# MicroPrimePCB.net
KiCad netlist of a schematic drawn in EAGLE
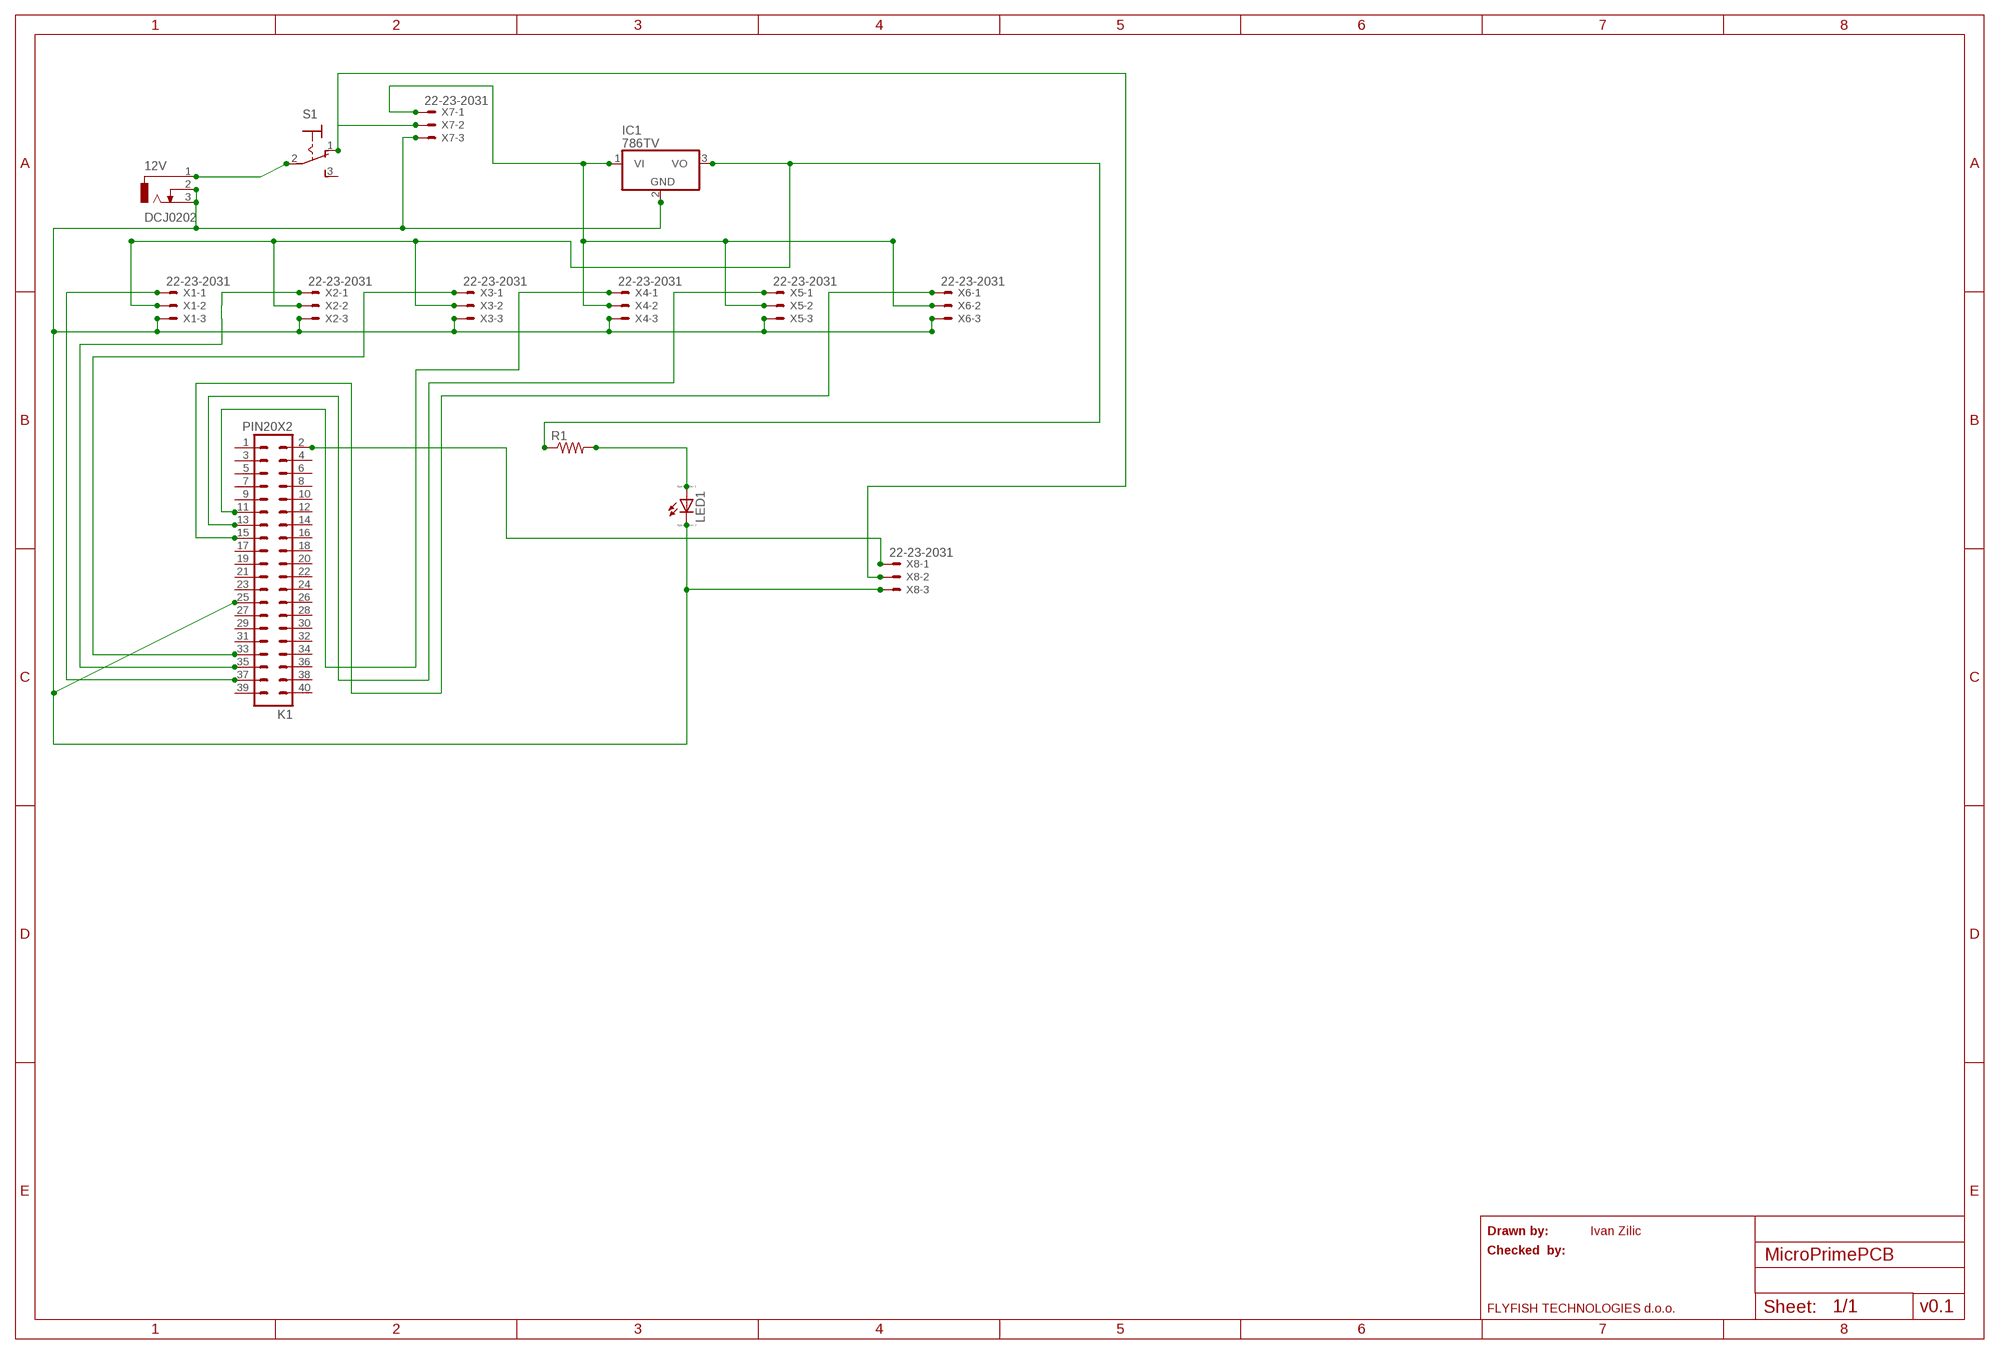
[diagram p0: schematic, sheet 1]

(export (version "E")
  (design (tool "Eeschema 10.0.6"))
  (components
    (comp (ref "12V")
      (value "DCJ0202")
      (footprint "eagle-import:DCJ0202")
      (libsource (lib "eagle-import") (part "DCJ0202"))
    )
    (comp (ref "IC1")
      (value "786TV")
      (footprint "eagle-import:TO220V")
      (libsource (lib "eagle-import") (part "78TV6"))
    )
    (comp (ref "K1")
      (value "PIN20X2")
      (footprint "eagle-import:PIN_20X2")
      (libsource (lib "eagle-import") (part "PIN20X2"))
    )
    (comp (ref "LED1")
      (value "LED_ELD260")
      (footprint "eagle-import:LED_LD260")
      (libsource (lib "eagle-import") (part "LED_ELD260"))
    )
    (comp (ref "R1")
      (value "R-US_0204/7")
      (footprint "eagle-import:0204_7")
      (libsource (lib "eagle-import") (part "R-US_0204/7"))
    )
    (comp (ref "S1")
      (value "320-916")
      (footprint "eagle-import:320-916")
      (libsource (lib "eagle-import") (part "320-916"))
    )
    (comp (ref "X1")
      (value "22-23-2031")
      (footprint "eagle-import:22-23-2031")
      (fields (field (name "MF") "MOLEX"))
      (libsource (lib "eagle-import") (part "22-23-2031"))
    )
    (comp (ref "X2")
      (value "22-23-2031")
      (footprint "eagle-import:22-23-2031")
      (fields (field (name "MF") "MOLEX"))
      (libsource (lib "eagle-import") (part "22-23-2031"))
    )
    (comp (ref "X3")
      (value "22-23-2031")
      (footprint "eagle-import:22-23-2031")
      (fields (field (name "MF") "MOLEX"))
      (libsource (lib "eagle-import") (part "22-23-2031"))
    )
    (comp (ref "X4")
      (value "22-23-2031")
      (footprint "eagle-import:22-23-2031")
      (fields (field (name "MF") "MOLEX"))
      (libsource (lib "eagle-import") (part "22-23-2031"))
    )
    (comp (ref "X5")
      (value "22-23-2031")
      (footprint "eagle-import:22-23-2031")
      (fields (field (name "MF") "MOLEX"))
      (libsource (lib "eagle-import") (part "22-23-2031"))
    )
    (comp (ref "X6")
      (value "22-23-2031")
      (footprint "eagle-import:22-23-2031")
      (fields (field (name "MF") "MOLEX"))
      (libsource (lib "eagle-import") (part "22-23-2031"))
    )
    (comp (ref "X7")
      (value "22-23-2031")
      (footprint "eagle-import:22-23-2031")
      (fields (field (name "MF") "MOLEX"))
      (libsource (lib "eagle-import") (part "22-23-2031"))
    )
    (comp (ref "X8")
      (value "22-23-2031")
      (footprint "eagle-import:22-23-2031")
      (fields (field (name "MF") "MOLEX"))
      (libsource (lib "eagle-import") (part "22-23-2031"))
    )
  )
  (nets
    (net (code "1") (name "Net-(IC1-GND)") (class "Default")
      (node (ref "12V") (pin "2") (pinfunction "2_2") (pintype "passive"))
      (node (ref "12V") (pin "3") (pinfunction "3_3") (pintype "passive"))
      (node (ref "IC1") (pin "2") (pinfunction "GND_2") (pintype "passive"))
      (node (ref "K1") (pin "25") (pinfunction "25_25") (pintype "passive"))
      (node (ref "LED1") (pin "K") (pinfunction "C_K") (pintype "passive"))
      (node (ref "X1") (pin "3") (pinfunction "S_3") (pintype "passive"))
      (node (ref "X2") (pin "3") (pinfunction "S_3") (pintype "passive"))
      (node (ref "X3") (pin "3") (pinfunction "S_3") (pintype "passive"))
      (node (ref "X4") (pin "3") (pinfunction "S_3") (pintype "passive"))
      (node (ref "X5") (pin "3") (pinfunction "S_3") (pintype "passive"))
      (node (ref "X6") (pin "3") (pinfunction "S_3") (pintype "passive"))
      (node (ref "X7") (pin "3") (pinfunction "S_3") (pintype "passive"))
      (node (ref "X8") (pin "3") (pinfunction "S_3") (pintype "passive"))
    )
    (net (code "2") (name "Net-(IC1-VI)") (class "Default")
      (node (ref "IC1") (pin "1") (pinfunction "VI_1") (pintype "input"))
      (node (ref "X4") (pin "2") (pinfunction "S_2") (pintype "passive"))
      (node (ref "X5") (pin "2") (pinfunction "S_2") (pintype "passive"))
      (node (ref "X6") (pin "2") (pinfunction "S_2") (pintype "passive"))
      (node (ref "X7") (pin "1") (pinfunction "S_1") (pintype "passive"))
    )
    (net (code "3") (name "Net-(IC1-VO)") (class "Default")
      (node (ref "IC1") (pin "3") (pinfunction "VO_3") (pintype "passive"))
      (node (ref "R1") (pin "1") (pinfunction "1_1") (pintype "passive"))
      (node (ref "X1") (pin "2") (pinfunction "S_2") (pintype "passive"))
      (node (ref "X2") (pin "2") (pinfunction "S_2") (pintype "passive"))
      (node (ref "X3") (pin "2") (pinfunction "S_2") (pintype "passive"))
    )
    (net (code "4") (name "Net-(LED1-PadA)") (class "Default")
      (node (ref "LED1") (pin "A") (pinfunction "A_A") (pintype "passive"))
      (node (ref "R1") (pin "2") (pinfunction "2_2") (pintype "passive"))
    )
    (net (code "5") (name "Net-(S1-O)") (class "Default")
      (node (ref "S1") (pin "1") (pinfunction "O_1") (pintype "passive"))
      (node (ref "X7") (pin "2") (pinfunction "S_2") (pintype "passive"))
      (node (ref "X8") (pin "2") (pinfunction "S_2") (pintype "passive"))
    )
    (net (code "6") (name "Net-(S1-P)") (class "Default")
      (node (ref "12V") (pin "1") (pinfunction "1_1") (pintype "passive"))
      (node (ref "S1") (pin "2") (pinfunction "P_2") (pintype "passive"))
    )
    (net (code "7") (name "Net-(X1A-S)") (class "Default")
      (node (ref "K1") (pin "37") (pinfunction "37_37") (pintype "passive"))
      (node (ref "X1") (pin "1") (pinfunction "S_1") (pintype "passive"))
    )
    (net (code "8") (name "Net-(X2A-S)") (class "Default")
      (node (ref "K1") (pin "35") (pinfunction "35_35") (pintype "passive"))
      (node (ref "X2") (pin "1") (pinfunction "S_1") (pintype "passive"))
    )
    (net (code "9") (name "Net-(X3A-S)") (class "Default")
      (node (ref "K1") (pin "33") (pinfunction "33_33") (pintype "passive"))
      (node (ref "X3") (pin "1") (pinfunction "S_1") (pintype "passive"))
    )
    (net (code "10") (name "Net-(X4A-S)") (class "Default")
      (node (ref "K1") (pin "11") (pinfunction "11_11") (pintype "passive"))
      (node (ref "X4") (pin "1") (pinfunction "S_1") (pintype "passive"))
    )
    (net (code "11") (name "Net-(X5A-S)") (class "Default")
      (node (ref "K1") (pin "13") (pinfunction "13_13") (pintype "passive"))
      (node (ref "X5") (pin "1") (pinfunction "S_1") (pintype "passive"))
    )
    (net (code "12") (name "Net-(X6A-S)") (class "Default")
      (node (ref "K1") (pin "15") (pinfunction "15_15") (pintype "passive"))
      (node (ref "X6") (pin "1") (pinfunction "S_1") (pintype "passive"))
    )
    (net (code "13") (name "Net-(X8A-S)") (class "Default")
      (node (ref "K1") (pin "2") (pinfunction "2_2") (pintype "passive"))
      (node (ref "X8") (pin "1") (pinfunction "S_1") (pintype "passive"))
    )
    (net (code "14") (name "unconnected-(K1-Pad1)") (class "Default")
      (node (ref "K1") (pin "1") (pinfunction "1_1") (pintype "passive"))
    )
    (net (code "15") (name "unconnected-(K1-Pad3)") (class "Default")
      (node (ref "K1") (pin "3") (pinfunction "3_3") (pintype "passive"))
    )
    (net (code "16") (name "unconnected-(K1-Pad4)") (class "Default")
      (node (ref "K1") (pin "4") (pinfunction "4_4") (pintype "passive"))
    )
    (net (code "17") (name "unconnected-(K1-Pad5)") (class "Default")
      (node (ref "K1") (pin "5") (pinfunction "5_5") (pintype "passive"))
    )
    (net (code "18") (name "unconnected-(K1-Pad6)") (class "Default")
      (node (ref "K1") (pin "6") (pinfunction "6_6") (pintype "passive"))
    )
    (net (code "19") (name "unconnected-(K1-Pad7)") (class "Default")
      (node (ref "K1") (pin "7") (pinfunction "7_7") (pintype "passive"))
    )
    (net (code "20") (name "unconnected-(K1-Pad8)") (class "Default")
      (node (ref "K1") (pin "8") (pinfunction "8_8") (pintype "passive"))
    )
    (net (code "21") (name "unconnected-(K1-Pad9)") (class "Default")
      (node (ref "K1") (pin "9") (pinfunction "9_9") (pintype "passive"))
    )
    (net (code "22") (name "unconnected-(K1-Pad10)") (class "Default")
      (node (ref "K1") (pin "10") (pinfunction "10_10") (pintype "passive"))
    )
    (net (code "23") (name "unconnected-(K1-Pad12)") (class "Default")
      (node (ref "K1") (pin "12") (pinfunction "12_12") (pintype "passive"))
    )
    (net (code "24") (name "unconnected-(K1-Pad14)") (class "Default")
      (node (ref "K1") (pin "14") (pinfunction "14_14") (pintype "passive"))
    )
    (net (code "25") (name "unconnected-(K1-Pad16)") (class "Default")
      (node (ref "K1") (pin "16") (pinfunction "16_16") (pintype "passive"))
    )
    (net (code "26") (name "unconnected-(K1-Pad17)") (class "Default")
      (node (ref "K1") (pin "17") (pinfunction "17_17") (pintype "passive"))
    )
    (net (code "27") (name "unconnected-(K1-Pad18)") (class "Default")
      (node (ref "K1") (pin "18") (pinfunction "18_18") (pintype "passive"))
    )
    (net (code "28") (name "unconnected-(K1-Pad19)") (class "Default")
      (node (ref "K1") (pin "19") (pinfunction "19_19") (pintype "passive"))
    )
    (net (code "29") (name "unconnected-(K1-Pad20)") (class "Default")
      (node (ref "K1") (pin "20") (pinfunction "20_20") (pintype "passive"))
    )
    (net (code "30") (name "unconnected-(K1-Pad21)") (class "Default")
      (node (ref "K1") (pin "21") (pinfunction "21_21") (pintype "passive"))
    )
    (net (code "31") (name "unconnected-(K1-Pad22)") (class "Default")
      (node (ref "K1") (pin "22") (pinfunction "22_22") (pintype "passive"))
    )
    (net (code "32") (name "unconnected-(K1-Pad23)") (class "Default")
      (node (ref "K1") (pin "23") (pinfunction "23_23") (pintype "passive"))
    )
    (net (code "33") (name "unconnected-(K1-Pad24)") (class "Default")
      (node (ref "K1") (pin "24") (pinfunction "24_24") (pintype "passive"))
    )
    (net (code "34") (name "unconnected-(K1-Pad26)") (class "Default")
      (node (ref "K1") (pin "26") (pinfunction "26_26") (pintype "passive"))
    )
    (net (code "35") (name "unconnected-(K1-Pad27)") (class "Default")
      (node (ref "K1") (pin "27") (pinfunction "27_27") (pintype "passive"))
    )
    (net (code "36") (name "unconnected-(K1-Pad28)") (class "Default")
      (node (ref "K1") (pin "28") (pinfunction "28_28") (pintype "passive"))
    )
    (net (code "37") (name "unconnected-(K1-Pad29)") (class "Default")
      (node (ref "K1") (pin "29") (pinfunction "29_29") (pintype "passive"))
    )
    (net (code "38") (name "unconnected-(K1-Pad30)") (class "Default")
      (node (ref "K1") (pin "30") (pinfunction "30_30") (pintype "passive"))
    )
    (net (code "39") (name "unconnected-(K1-Pad31)") (class "Default")
      (node (ref "K1") (pin "31") (pinfunction "31_31") (pintype "passive"))
    )
    (net (code "40") (name "unconnected-(K1-Pad32)") (class "Default")
      (node (ref "K1") (pin "32") (pinfunction "32_32") (pintype "passive"))
    )
    (net (code "41") (name "unconnected-(K1-Pad34)") (class "Default")
      (node (ref "K1") (pin "34") (pinfunction "34_34") (pintype "passive"))
    )
    (net (code "42") (name "unconnected-(K1-Pad36)") (class "Default")
      (node (ref "K1") (pin "36") (pinfunction "36_36") (pintype "passive"))
    )
    (net (code "43") (name "unconnected-(K1-Pad38)") (class "Default")
      (node (ref "K1") (pin "38") (pinfunction "38_38") (pintype "passive"))
    )
    (net (code "44") (name "unconnected-(K1-Pad39)") (class "Default")
      (node (ref "K1") (pin "39") (pinfunction "39_39") (pintype "passive"))
    )
    (net (code "45") (name "unconnected-(K1-Pad40)") (class "Default")
      (node (ref "K1") (pin "40") (pinfunction "40_40") (pintype "passive"))
    )
    (net (code "46") (name "unconnected-(S1-S-Pad3)") (class "Default")
      (node (ref "S1") (pin "3") (pinfunction "S_3") (pintype "passive"))
    )
  )
)
